# TMS320C5509A.net
KiCad netlist of a schematic drawn in Altium Designer
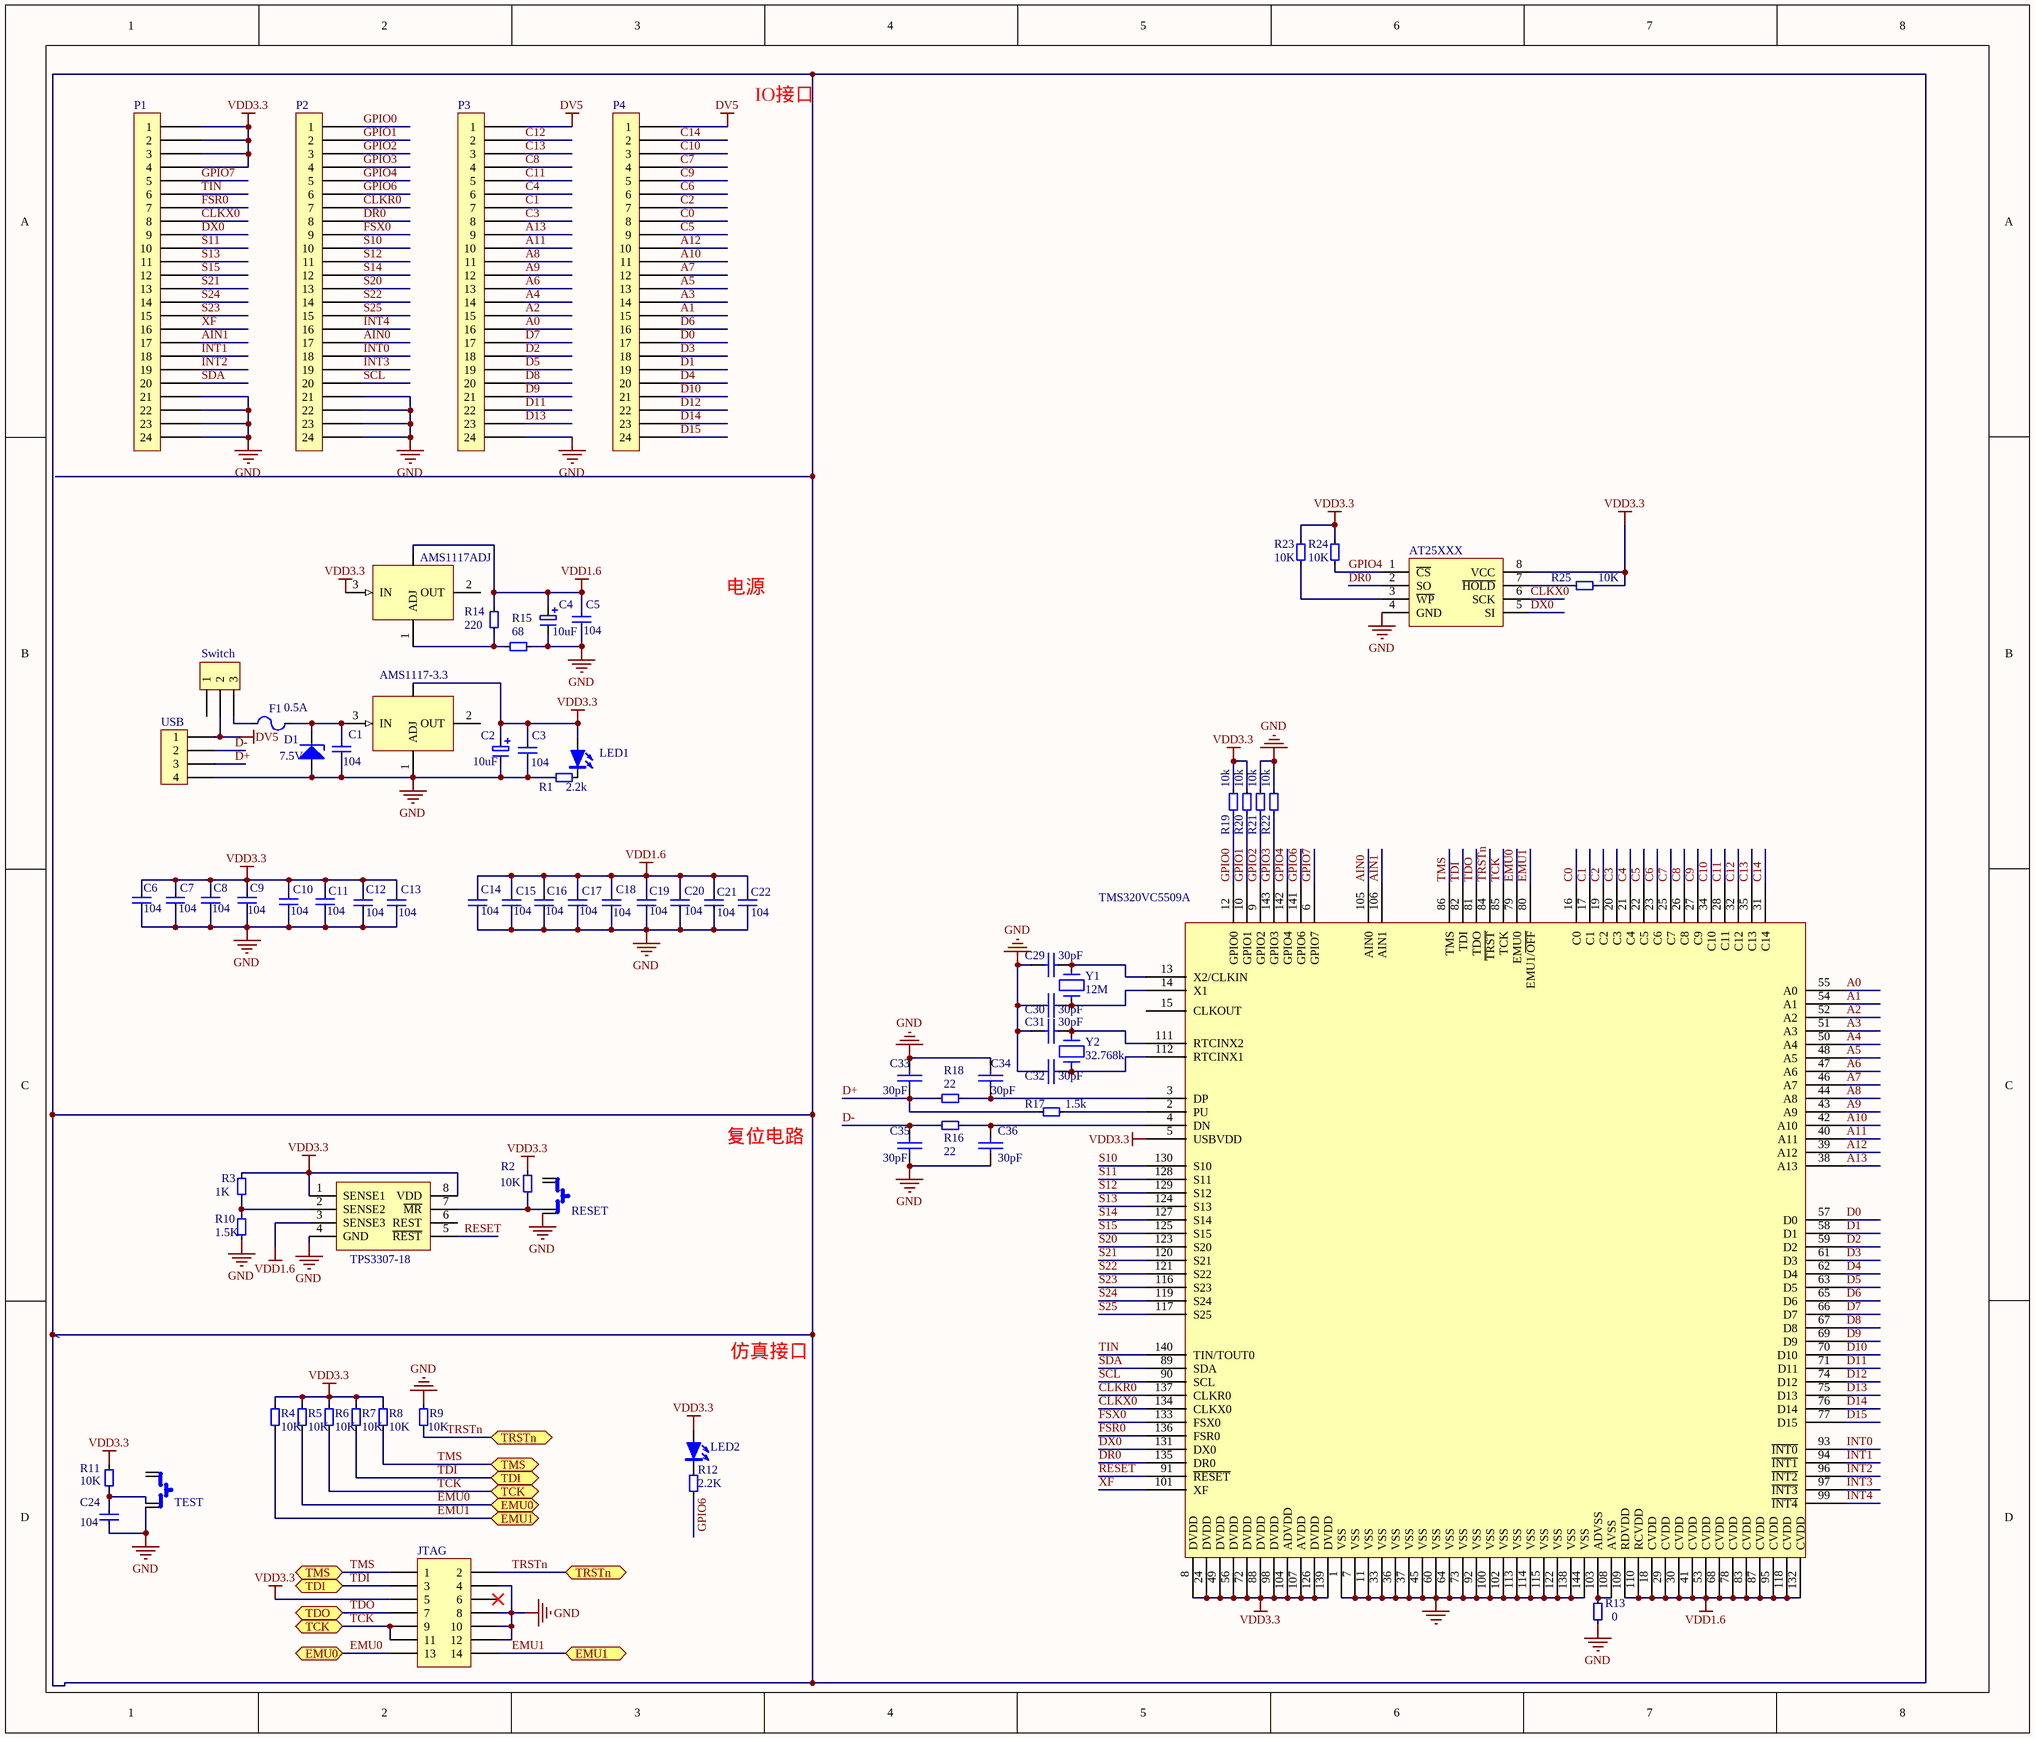
[diagram p0: TMS320C5509A.SchDoc]

(export (version "E")
  (design (tool "Eeschema 10.0.6"))
  (components
    (comp (ref "AMS1117-3.3") (value "1117") (footprint "SOT-223") (libsource (lib "电源（专用）") (part "1117")))
    (comp (ref "AMS1117ADJ") (value "1117") (footprint "SOT-223") (libsource (lib "电源（专用）") (part "1117")))
    (comp (ref "AT25XXX") (value "~") (libsource (lib "Common") (part "AT25XXX")))
    (comp (ref "C1") (value "104") (footprint "0805") (libsource (lib "电容系列") (part "C3")))
    (comp (ref "C2") (value "10uF") (footprint "CE3528") (libsource (lib "电容系列") (part "E3")))
    (comp (ref "C3") (value "104") (footprint "0805") (libsource (lib "电容系列") (part "C3")))
    (comp (ref "C4") (value "10uF") (footprint "CE3528") (libsource (lib "电容系列") (part "E3")))
    (comp (ref "C5") (value "104") (footprint "0805") (libsource (lib "电容系列") (part "C3")))
    (comp (ref "C6") (value "104") (footprint "0805") (libsource (lib "电容系列") (part "C3")))
    (comp (ref "C7") (value "104") (footprint "0805") (libsource (lib "电容系列") (part "C3")))
    (comp (ref "C8") (value "104") (footprint "0805") (libsource (lib "电容系列") (part "C3")))
    (comp (ref "C9") (value "104") (footprint "0805") (libsource (lib "电容系列") (part "C3")))
    (comp (ref "C10") (value "104") (footprint "0805") (libsource (lib "电容系列") (part "C3")))
    (comp (ref "C11") (value "104") (footprint "0805") (libsource (lib "电容系列") (part "C3")))
    (comp (ref "C12") (value "104") (footprint "0805") (libsource (lib "电容系列") (part "C3")))
    (comp (ref "C13") (value "104") (footprint "0805") (libsource (lib "电容系列") (part "C3")))
    (comp (ref "C14") (value "104") (footprint "0805") (libsource (lib "电容系列") (part "C3")))
    (comp (ref "C15") (value "104") (footprint "0805") (libsource (lib "电容系列") (part "C3")))
    (comp (ref "C16") (value "104") (footprint "0805") (libsource (lib "电容系列") (part "C3")))
    (comp (ref "C17") (value "104") (footprint "0805") (libsource (lib "电容系列") (part "C3")))
    (comp (ref "C18") (value "104") (footprint "0805") (libsource (lib "电容系列") (part "C3")))
    (comp (ref "C19") (value "104") (footprint "0805") (libsource (lib "电容系列") (part "C3")))
    (comp (ref "C20") (value "104") (footprint "0805") (libsource (lib "电容系列") (part "C3")))
    (comp (ref "C21") (value "104") (footprint "0805") (libsource (lib "电容系列") (part "C3")))
    (comp (ref "C22") (value "104") (footprint "0805") (libsource (lib "电容系列") (part "C3")))
    (comp (ref "C24") (value "104") (footprint "0805") (libsource (lib "电容系列") (part "C3")))
    (comp (ref "C29") (value "30pF") (footprint "0805") (libsource (lib "电容系列") (part "C1")))
    (comp (ref "C30") (value "30pF") (footprint "0805") (libsource (lib "电容系列") (part "C1")))
    (comp (ref "C31") (value "30pF") (footprint "0805") (libsource (lib "电容系列") (part "C1")))
    (comp (ref "C32") (value "30pF") (footprint "0805") (libsource (lib "电容系列") (part "C1")))
    (comp (ref "C33") (value "30pF") (footprint "0805") (libsource (lib "电容系列") (part "C1")))
    (comp (ref "C34") (value "30pF") (footprint "0805") (libsource (lib "电容系列") (part "C1")))
    (comp (ref "C35") (value "30pF") (footprint "0805") (libsource (lib "电容系列") (part "C1")))
    (comp (ref "C36") (value "30pF") (footprint "0805") (libsource (lib "电容系列") (part "C1")))
    (comp (ref "D1") (value "7.5V") (footprint "1206") (libsource (lib "二极管") (part "D4")))
    (comp (ref "F1") (value "0.5A") (footprint "F4532") (libsource (lib "常用库") (part "FUSE1")))
    (comp (ref "JTAG")
      (value "Header 7X2")
      (footprint "IDC14A")
      (description "Header, 7-Pin, Dual row")
      (fields (field (name "PUBLISHER") "Altium Limited"))
      (libsource (lib "myproject") (part "Header 7X2"))
    )
    (comp (ref "LED1") (value "LED2") (footprint "0805") (libsource (lib "发光管、数码管") (part "LED2")))
    (comp (ref "LED2") (value "LED2") (footprint "0805") (libsource (lib "发光管、数码管") (part "LED2")))
    (comp (ref "P1") (value "SIP24") (footprint "SIP24") (libsource (lib "SIP2.54") (part "SIP24")))
    (comp (ref "P2") (value "SIP24") (footprint "SIP24") (libsource (lib "SIP2.54") (part "SIP24")))
    (comp (ref "P3") (value "SIP24") (footprint "SIP24") (libsource (lib "SIP2.54") (part "SIP24")))
    (comp (ref "P4") (value "SIP24") (footprint "SIP24") (libsource (lib "SIP2.54") (part "SIP24")))
    (comp (ref "R1") (value "2.2k") (footprint "0805") (libsource (lib "电阻系列") (part "R3")))
    (comp (ref "R2") (value "10K") (footprint "0805") (libsource (lib "电阻系列") (part "R3")))
    (comp (ref "R3") (value "1K") (footprint "0805") (libsource (lib "电阻系列") (part "R3")))
    (comp (ref "R4") (value "10K") (footprint "0805") (libsource (lib "电阻系列") (part "R3")))
    (comp (ref "R5") (value "10K") (footprint "0805") (libsource (lib "电阻系列") (part "R3")))
    (comp (ref "R6") (value "10K") (footprint "0805") (libsource (lib "电阻系列") (part "R3")))
    (comp (ref "R7") (value "10K") (footprint "0805") (libsource (lib "电阻系列") (part "R3")))
    (comp (ref "R8") (value "10K") (footprint "0805") (libsource (lib "电阻系列") (part "R3")))
    (comp (ref "R9") (value "10K") (footprint "0805") (libsource (lib "电阻系列") (part "R3")))
    (comp (ref "R10") (value "1.5K") (footprint "0805") (libsource (lib "电阻系列") (part "R3")))
    (comp (ref "R11") (value "10K") (footprint "0805") (libsource (lib "电阻系列") (part "R3")))
    (comp (ref "R12") (value "2.2K") (footprint "0805") (libsource (lib "电阻系列") (part "R3")))
    (comp (ref "R13") (value "0") (footprint "0805") (libsource (lib "电阻系列") (part "R3")))
    (comp (ref "R14") (value "220") (footprint "0805") (libsource (lib "电阻系列") (part "R3")))
    (comp (ref "R15") (value "68") (footprint "0805") (libsource (lib "电阻系列") (part "R3")))
    (comp (ref "R16") (value "22") (footprint "0805") (libsource (lib "电阻系列") (part "R3")))
    (comp (ref "R17") (value "1.5k") (footprint "0805") (libsource (lib "电阻系列") (part "R3")))
    (comp (ref "R18") (value "22") (footprint "0805") (libsource (lib "电阻系列") (part "R3")))
    (comp (ref "R19") (value "10k") (footprint "0805") (libsource (lib "电阻系列") (part "R3")))
    (comp (ref "R20") (value "10k") (footprint "0805") (libsource (lib "电阻系列") (part "R3")))
    (comp (ref "R21") (value "10k") (footprint "0805") (libsource (lib "电阻系列") (part "R3")))
    (comp (ref "R22") (value "10k") (footprint "0805") (libsource (lib "电阻系列") (part "R3")))
    (comp (ref "R23") (value "10K") (footprint "0805") (libsource (lib "电阻系列") (part "R3")))
    (comp (ref "R24") (value "10K") (footprint "0805") (libsource (lib "电阻系列") (part "R3")))
    (comp (ref "R25") (value "10K") (footprint "0805") (libsource (lib "电阻系列") (part "R3")))
    (comp (ref "RESET") (value "KEY2") (footprint "KEY0.2'") (libsource (lib "常用库") (part "KEY2")))
    (comp (ref "Switch") (value "CON3") (footprint "船型三脚开关:5脚船型开关") (libsource (lib "常用接插件") (part "CON3")))
    (comp (ref "TEST") (value "KEY2") (footprint "KEY0.2'") (libsource (lib "常用库") (part "KEY2")))
    (comp (ref "TMS320VC5509A")
      (value "TMS320VC5509A")
      (footprint "TMS320LV5410")
      (description "TMS320VC5509")
      (libsource (lib "*") (part "TMS320VC5509A"))
    )
    (comp (ref "TPS3307-18") (value "~") (footprint "SOP8") (libsource (lib "myproject") (part "TPS3307-18")))
    (comp (ref "USB") (value "CON4") (footprint "USB2") (libsource (lib "常用接插件") (part "CON4")))
    (comp (ref "Y1") (value "12M") (footprint "CY1") (libsource (lib "常用库") (part "CY1")))
    (comp (ref "Y2") (value "32.768k") (footprint "CY1") (libsource (lib "常用库") (part "CY1")))
  )
  (nets
    (net (code "1") (name "/A0") (class "Default")
      (node (ref "P3") (pin "16") (pinfunction "16_16") (pintype "passive"))
      (node (ref "TMS320VC5509A") (pin "55") (pinfunction "A0_55") (pintype "passive"))
    )
    (net (code "2") (name "/A1") (class "Default")
      (node (ref "P4") (pin "15") (pinfunction "15_15") (pintype "passive"))
      (node (ref "TMS320VC5509A") (pin "54") (pinfunction "A1_54") (pintype "passive"))
    )
    (net (code "3") (name "/A2") (class "Default")
      (node (ref "P3") (pin "15") (pinfunction "15_15") (pintype "passive"))
      (node (ref "TMS320VC5509A") (pin "52") (pinfunction "A2_52") (pintype "passive"))
    )
    (net (code "4") (name "/A3") (class "Default")
      (node (ref "P4") (pin "14") (pinfunction "14_14") (pintype "passive"))
      (node (ref "TMS320VC5509A") (pin "51") (pinfunction "A3_51") (pintype "passive"))
    )
    (net (code "5") (name "/A4") (class "Default")
      (node (ref "P3") (pin "14") (pinfunction "14_14") (pintype "passive"))
      (node (ref "TMS320VC5509A") (pin "50") (pinfunction "A4_50") (pintype "passive"))
    )
    (net (code "6") (name "/A5") (class "Default")
      (node (ref "P4") (pin "13") (pinfunction "13_13") (pintype "passive"))
      (node (ref "TMS320VC5509A") (pin "48") (pinfunction "A5_48") (pintype "passive"))
    )
    (net (code "7") (name "/A6") (class "Default")
      (node (ref "P3") (pin "13") (pinfunction "13_13") (pintype "passive"))
      (node (ref "TMS320VC5509A") (pin "47") (pinfunction "A6_47") (pintype "passive"))
    )
    (net (code "8") (name "/A7") (class "Default")
      (node (ref "P4") (pin "12") (pinfunction "12_12") (pintype "passive"))
      (node (ref "TMS320VC5509A") (pin "46") (pinfunction "A7_46") (pintype "passive"))
    )
    (net (code "9") (name "/A8") (class "Default")
      (node (ref "P3") (pin "11") (pinfunction "11_11") (pintype "passive"))
      (node (ref "TMS320VC5509A") (pin "44") (pinfunction "A8_44") (pintype "passive"))
    )
    (net (code "10") (name "/A9") (class "Default")
      (node (ref "P3") (pin "12") (pinfunction "12_12") (pintype "passive"))
      (node (ref "TMS320VC5509A") (pin "43") (pinfunction "A9_43") (pintype "passive"))
    )
    (net (code "11") (name "/A10") (class "Default")
      (node (ref "P4") (pin "11") (pinfunction "11_11") (pintype "passive"))
      (node (ref "TMS320VC5509A") (pin "42") (pinfunction "A10_42") (pintype "passive"))
    )
    (net (code "12") (name "/A11") (class "Default")
      (node (ref "P3") (pin "10") (pinfunction "10_10") (pintype "passive"))
      (node (ref "TMS320VC5509A") (pin "40") (pinfunction "A11_40") (pintype "passive"))
    )
    (net (code "13") (name "/A12") (class "Default")
      (node (ref "P4") (pin "10") (pinfunction "10_10") (pintype "passive"))
      (node (ref "TMS320VC5509A") (pin "39") (pinfunction "A12_39") (pintype "passive"))
    )
    (net (code "14") (name "/A13") (class "Default")
      (node (ref "P3") (pin "9") (pinfunction "9_9") (pintype "passive"))
      (node (ref "TMS320VC5509A") (pin "38") (pinfunction "A13_38") (pintype "passive"))
    )
    (net (code "15") (name "/AIN0") (class "Default")
      (node (ref "P2") (pin "17") (pinfunction "17_17") (pintype "passive"))
      (node (ref "TMS320VC5509A") (pin "105") (pinfunction "AIN0_105") (pintype "passive"))
    )
    (net (code "16") (name "/AIN1") (class "Default")
      (node (ref "P1") (pin "17") (pinfunction "17_17") (pintype "passive"))
      (node (ref "TMS320VC5509A") (pin "106") (pinfunction "AIN1_106") (pintype "passive"))
    )
    (net (code "17") (name "/C0") (class "Default")
      (node (ref "P4") (pin "8") (pinfunction "8_8") (pintype "passive"))
      (node (ref "TMS320VC5509A") (pin "16") (pinfunction "C0_16") (pintype "passive"))
    )
    (net (code "18") (name "/C1") (class "Default")
      (node (ref "P3") (pin "7") (pinfunction "7_7") (pintype "passive"))
      (node (ref "TMS320VC5509A") (pin "17") (pinfunction "C1_17") (pintype "passive"))
    )
    (net (code "19") (name "/C2") (class "Default")
      (node (ref "P4") (pin "7") (pinfunction "7_7") (pintype "passive"))
      (node (ref "TMS320VC5509A") (pin "19") (pinfunction "C2_19") (pintype "passive"))
    )
    (net (code "20") (name "/C3") (class "Default")
      (node (ref "P3") (pin "8") (pinfunction "8_8") (pintype "passive"))
      (node (ref "TMS320VC5509A") (pin "20") (pinfunction "C3_20") (pintype "passive"))
    )
    (net (code "21") (name "/C4") (class "Default")
      (node (ref "P3") (pin "6") (pinfunction "6_6") (pintype "passive"))
      (node (ref "TMS320VC5509A") (pin "21") (pinfunction "C4_21") (pintype "passive"))
    )
    (net (code "22") (name "/C5") (class "Default")
      (node (ref "P4") (pin "9") (pinfunction "9_9") (pintype "passive"))
      (node (ref "TMS320VC5509A") (pin "22") (pinfunction "C5_22") (pintype "passive"))
    )
    (net (code "23") (name "/C6") (class "Default")
      (node (ref "P4") (pin "6") (pinfunction "6_6") (pintype "passive"))
      (node (ref "TMS320VC5509A") (pin "23") (pinfunction "C6_23") (pintype "passive"))
    )
    (net (code "24") (name "/C7") (class "Default")
      (node (ref "P4") (pin "4") (pinfunction "4_4") (pintype "passive"))
      (node (ref "TMS320VC5509A") (pin "25") (pinfunction "C7_25") (pintype "passive"))
    )
    (net (code "25") (name "/C8") (class "Default")
      (node (ref "P3") (pin "4") (pinfunction "4_4") (pintype "passive"))
      (node (ref "TMS320VC5509A") (pin "26") (pinfunction "C8_26") (pintype "passive"))
    )
    (net (code "26") (name "/C9") (class "Default")
      (node (ref "P4") (pin "5") (pinfunction "5_5") (pintype "passive"))
      (node (ref "TMS320VC5509A") (pin "27") (pinfunction "C9_27") (pintype "passive"))
    )
    (net (code "27") (name "/C10") (class "Default")
      (node (ref "P4") (pin "3") (pinfunction "3_3") (pintype "passive"))
      (node (ref "TMS320VC5509A") (pin "34") (pinfunction "C10_34") (pintype "passive"))
    )
    (net (code "28") (name "/C11") (class "Default")
      (node (ref "P3") (pin "5") (pinfunction "5_5") (pintype "passive"))
      (node (ref "TMS320VC5509A") (pin "28") (pinfunction "C11_28") (pintype "passive"))
    )
    (net (code "29") (name "/C12") (class "Default")
      (node (ref "P3") (pin "2") (pinfunction "2_2") (pintype "passive"))
      (node (ref "TMS320VC5509A") (pin "32") (pinfunction "C12_32") (pintype "passive"))
    )
    (net (code "30") (name "/C13") (class "Default")
      (node (ref "P3") (pin "3") (pinfunction "3_3") (pintype "passive"))
      (node (ref "TMS320VC5509A") (pin "35") (pinfunction "C13_35") (pintype "passive"))
    )
    (net (code "31") (name "/C14") (class "Default")
      (node (ref "P4") (pin "2") (pinfunction "2_2") (pintype "passive"))
      (node (ref "TMS320VC5509A") (pin "31") (pinfunction "C14_31") (pintype "passive"))
    )
    (net (code "32") (name "/CLKR0") (class "Default")
      (node (ref "P2") (pin "7") (pinfunction "7_7") (pintype "passive"))
      (node (ref "TMS320VC5509A") (pin "137") (pinfunction "CLKR0_137") (pintype "passive"))
    )
    (net (code "33") (name "/CLKX0") (class "Default")
      (node (ref "AT25XXX") (pin "6") (pinfunction "SCK_6") (pintype "passive"))
      (node (ref "P1") (pin "8") (pinfunction "8_8") (pintype "passive"))
      (node (ref "TMS320VC5509A") (pin "134") (pinfunction "CLKX0_134") (pintype "passive"))
    )
    (net (code "34") (name "/D+") (class "Default")
      (node (ref "C33") (pin "2") (pinfunction "2_2") (pintype "passive"))
      (node (ref "R17") (pin "2") (pinfunction "2_2") (pintype "passive"))
      (node (ref "R18") (pin "2") (pinfunction "2_2") (pintype "passive"))
      (node (ref "USB") (pin "3") (pinfunction "3_3") (pintype "passive"))
    )
    (net (code "35") (name "/D-") (class "Default")
      (node (ref "C35") (pin "2") (pinfunction "2_2") (pintype "passive"))
      (node (ref "R16") (pin "2") (pinfunction "2_2") (pintype "passive"))
      (node (ref "USB") (pin "2") (pinfunction "2_2") (pintype "passive"))
    )
    (net (code "36") (name "/D0") (class "Default")
      (node (ref "P4") (pin "17") (pinfunction "17_17") (pintype "passive"))
      (node (ref "TMS320VC5509A") (pin "57") (pinfunction "D0_57") (pintype "passive"))
    )
    (net (code "37") (name "/D1") (class "Default")
      (node (ref "P4") (pin "19") (pinfunction "19_19") (pintype "passive"))
      (node (ref "TMS320VC5509A") (pin "58") (pinfunction "D1_58") (pintype "passive"))
    )
    (net (code "38") (name "/D2") (class "Default")
      (node (ref "P3") (pin "18") (pinfunction "18_18") (pintype "passive"))
      (node (ref "TMS320VC5509A") (pin "59") (pinfunction "D2_59") (pintype "passive"))
    )
    (net (code "39") (name "/D3") (class "Default")
      (node (ref "P4") (pin "18") (pinfunction "18_18") (pintype "passive"))
      (node (ref "TMS320VC5509A") (pin "61") (pinfunction "D3_61") (pintype "passive"))
    )
    (net (code "40") (name "/D4") (class "Default")
      (node (ref "P4") (pin "20") (pinfunction "20_20") (pintype "passive"))
      (node (ref "TMS320VC5509A") (pin "62") (pinfunction "D4_62") (pintype "passive"))
    )
    (net (code "41") (name "/D5") (class "Default")
      (node (ref "P3") (pin "19") (pinfunction "19_19") (pintype "passive"))
      (node (ref "TMS320VC5509A") (pin "63") (pinfunction "D5_63") (pintype "passive"))
    )
    (net (code "42") (name "/D6") (class "Default")
      (node (ref "P4") (pin "16") (pinfunction "16_16") (pintype "passive"))
      (node (ref "TMS320VC5509A") (pin "65") (pinfunction "D6_65") (pintype "passive"))
    )
    (net (code "43") (name "/D7") (class "Default")
      (node (ref "P3") (pin "17") (pinfunction "17_17") (pintype "passive"))
      (node (ref "TMS320VC5509A") (pin "66") (pinfunction "D7_66") (pintype "passive"))
    )
    (net (code "44") (name "/D8") (class "Default")
      (node (ref "P3") (pin "20") (pinfunction "20_20") (pintype "passive"))
      (node (ref "TMS320VC5509A") (pin "67") (pinfunction "D8_67") (pintype "passive"))
    )
    (net (code "45") (name "/D9") (class "Default")
      (node (ref "P3") (pin "21") (pinfunction "21_21") (pintype "passive"))
      (node (ref "TMS320VC5509A") (pin "69") (pinfunction "D9_69") (pintype "passive"))
    )
    (net (code "46") (name "/D10") (class "Default")
      (node (ref "P4") (pin "21") (pinfunction "21_21") (pintype "passive"))
      (node (ref "TMS320VC5509A") (pin "70") (pinfunction "D10_70") (pintype "passive"))
    )
    (net (code "47") (name "/D11") (class "Default")
      (node (ref "P3") (pin "22") (pinfunction "22_22") (pintype "passive"))
      (node (ref "TMS320VC5509A") (pin "71") (pinfunction "D11_71") (pintype "passive"))
    )
    (net (code "48") (name "/D12") (class "Default")
      (node (ref "P4") (pin "22") (pinfunction "22_22") (pintype "passive"))
      (node (ref "TMS320VC5509A") (pin "74") (pinfunction "D12_74") (pintype "passive"))
    )
    (net (code "49") (name "/D13") (class "Default")
      (node (ref "P3") (pin "23") (pinfunction "23_23") (pintype "passive"))
      (node (ref "TMS320VC5509A") (pin "75") (pinfunction "D13_75") (pintype "passive"))
    )
    (net (code "50") (name "/D14") (class "Default")
      (node (ref "P4") (pin "23") (pinfunction "23_23") (pintype "passive"))
      (node (ref "TMS320VC5509A") (pin "76") (pinfunction "D14_76") (pintype "passive"))
    )
    (net (code "51") (name "/D15") (class "Default")
      (node (ref "P4") (pin "24") (pinfunction "24_24") (pintype "passive"))
      (node (ref "TMS320VC5509A") (pin "77") (pinfunction "D15_77") (pintype "passive"))
    )
    (net (code "52") (name "/DR0") (class "Default")
      (node (ref "AT25XXX") (pin "2") (pinfunction "SO_2") (pintype "passive"))
      (node (ref "P2") (pin "8") (pinfunction "8_8") (pintype "passive"))
      (node (ref "TMS320VC5509A") (pin "135") (pinfunction "DR0_135") (pintype "passive"))
    )
    (net (code "53") (name "/DX0") (class "Default")
      (node (ref "AT25XXX") (pin "5") (pinfunction "SI_5") (pintype "passive"))
      (node (ref "P1") (pin "9") (pinfunction "9_9") (pintype "passive"))
      (node (ref "TMS320VC5509A") (pin "131") (pinfunction "DX0_131") (pintype "passive"))
    )
    (net (code "54") (name "/EMU0") (class "Default")
      (node (ref "JTAG") (pin "13") (pinfunction "13_13") (pintype "passive"))
      (node (ref "R5") (pin "1") (pinfunction "1_1") (pintype "passive"))
      (node (ref "TMS320VC5509A") (pin "79") (pinfunction "EMU0_79") (pintype "passive"))
    )
    (net (code "55") (name "/EMU1") (class "Default")
      (node (ref "JTAG") (pin "14") (pinfunction "14_14") (pintype "passive"))
      (node (ref "R4") (pin "1") (pinfunction "1_1") (pintype "passive"))
      (node (ref "TMS320VC5509A") (pin "80") (pinfunction "EMU1/~{OFF}_80") (pintype "passive"))
    )
    (net (code "56") (name "/FSR0") (class "Default")
      (node (ref "P1") (pin "7") (pinfunction "7_7") (pintype "passive"))
      (node (ref "TMS320VC5509A") (pin "136") (pinfunction "FSR0_136") (pintype "passive"))
    )
    (net (code "57") (name "/FSX0") (class "Default")
      (node (ref "P2") (pin "9") (pinfunction "9_9") (pintype "passive"))
      (node (ref "TMS320VC5509A") (pin "133") (pinfunction "FSX0_133") (pintype "passive"))
    )
    (net (code "58") (name "/GPIO0") (class "Default")
      (node (ref "P2") (pin "1") (pinfunction "1_1") (pintype "passive"))
      (node (ref "R19") (pin "2") (pinfunction "2_2") (pintype "passive"))
      (node (ref "TMS320VC5509A") (pin "12") (pinfunction "GPIO0_12") (pintype "passive"))
    )
    (net (code "59") (name "/GPIO1") (class "Default")
      (node (ref "P2") (pin "2") (pinfunction "2_2") (pintype "passive"))
      (node (ref "R20") (pin "2") (pinfunction "2_2") (pintype "passive"))
      (node (ref "TMS320VC5509A") (pin "10") (pinfunction "GPIO1_10") (pintype "passive"))
    )
    (net (code "60") (name "/GPIO2") (class "Default")
      (node (ref "P2") (pin "3") (pinfunction "3_3") (pintype "passive"))
      (node (ref "R21") (pin "2") (pinfunction "2_2") (pintype "passive"))
      (node (ref "TMS320VC5509A") (pin "9") (pinfunction "GPIO2_9") (pintype "passive"))
    )
    (net (code "61") (name "/GPIO3") (class "Default")
      (node (ref "P2") (pin "4") (pinfunction "4_4") (pintype "passive"))
      (node (ref "R22") (pin "2") (pinfunction "2_2") (pintype "passive"))
      (node (ref "TMS320VC5509A") (pin "143") (pinfunction "GPIO3_143") (pintype "passive"))
    )
    (net (code "62") (name "/GPIO4") (class "Default")
      (node (ref "AT25XXX") (pin "1") (pinfunction "~{CS}_1") (pintype "passive"))
      (node (ref "P2") (pin "5") (pinfunction "5_5") (pintype "passive"))
      (node (ref "R24") (pin "1") (pinfunction "1_1") (pintype "passive"))
      (node (ref "TMS320VC5509A") (pin "142") (pinfunction "GPIO4_142") (pintype "passive"))
    )
    (net (code "63") (name "/GPIO6") (class "Default")
      (node (ref "P2") (pin "6") (pinfunction "6_6") (pintype "passive"))
      (node (ref "R12") (pin "2") (pinfunction "2_2") (pintype "passive"))
      (node (ref "TMS320VC5509A") (pin "141") (pinfunction "GPIO6_141") (pintype "passive"))
    )
    (net (code "64") (name "/GPIO7") (class "Default")
      (node (ref "P1") (pin "5") (pinfunction "5_5") (pintype "passive"))
      (node (ref "TMS320VC5509A") (pin "6") (pinfunction "GPIO7_6") (pintype "passive"))
    )
    (net (code "65") (name "/INT0") (class "Default")
      (node (ref "P2") (pin "18") (pinfunction "18_18") (pintype "passive"))
      (node (ref "TMS320VC5509A") (pin "93") (pinfunction "~{INT0}_93") (pintype "passive"))
    )
    (net (code "66") (name "/INT1") (class "Default")
      (node (ref "P1") (pin "18") (pinfunction "18_18") (pintype "passive"))
      (node (ref "TMS320VC5509A") (pin "94") (pinfunction "~{INT1}_94") (pintype "passive"))
    )
    (net (code "67") (name "/INT2") (class "Default")
      (node (ref "P1") (pin "19") (pinfunction "19_19") (pintype "passive"))
      (node (ref "TMS320VC5509A") (pin "96") (pinfunction "~{INT2}_96") (pintype "passive"))
    )
    (net (code "68") (name "/INT3") (class "Default")
      (node (ref "P2") (pin "19") (pinfunction "19_19") (pintype "passive"))
      (node (ref "TMS320VC5509A") (pin "97") (pinfunction "~{INT3}_97") (pintype "passive"))
    )
    (net (code "69") (name "/INT4") (class "Default")
      (node (ref "P2") (pin "16") (pinfunction "16_16") (pintype "passive"))
      (node (ref "TMS320VC5509A") (pin "99") (pinfunction "~{INT4}_99") (pintype "passive"))
    )
    (net (code "70") (name "/RESET") (class "Default")
      (node (ref "TMS320VC5509A") (pin "91") (pinfunction "~{RESET}_91") (pintype "passive"))
      (node (ref "TPS3307-18") (pin "5") (pinfunction "~{REST}_5") (pintype "passive"))
    )
    (net (code "71") (name "/S10") (class "Default")
      (node (ref "P2") (pin "10") (pinfunction "10_10") (pintype "passive"))
      (node (ref "TMS320VC5509A") (pin "130") (pinfunction "S10_130") (pintype "passive"))
    )
    (net (code "72") (name "/S11") (class "Default")
      (node (ref "P1") (pin "10") (pinfunction "10_10") (pintype "passive"))
      (node (ref "TMS320VC5509A") (pin "128") (pinfunction "S11_128") (pintype "passive"))
    )
    (net (code "73") (name "/S12") (class "Default")
      (node (ref "P2") (pin "11") (pinfunction "11_11") (pintype "passive"))
      (node (ref "TMS320VC5509A") (pin "129") (pinfunction "S12_129") (pintype "passive"))
    )
    (net (code "74") (name "/S13") (class "Default")
      (node (ref "P1") (pin "11") (pinfunction "11_11") (pintype "passive"))
      (node (ref "TMS320VC5509A") (pin "124") (pinfunction "S13_124") (pintype "passive"))
    )
    (net (code "75") (name "/S14") (class "Default")
      (node (ref "P2") (pin "12") (pinfunction "12_12") (pintype "passive"))
      (node (ref "TMS320VC5509A") (pin "127") (pinfunction "S14_127") (pintype "passive"))
    )
    (net (code "76") (name "/S15") (class "Default")
      (node (ref "P1") (pin "12") (pinfunction "12_12") (pintype "passive"))
      (node (ref "TMS320VC5509A") (pin "125") (pinfunction "S15_125") (pintype "passive"))
    )
    (net (code "77") (name "/S20") (class "Default")
      (node (ref "P2") (pin "13") (pinfunction "13_13") (pintype "passive"))
      (node (ref "TMS320VC5509A") (pin "123") (pinfunction "S20_123") (pintype "passive"))
    )
    (net (code "78") (name "/S21") (class "Default")
      (node (ref "P1") (pin "13") (pinfunction "13_13") (pintype "passive"))
      (node (ref "TMS320VC5509A") (pin "120") (pinfunction "S21_120") (pintype "passive"))
    )
    (net (code "79") (name "/S22") (class "Default")
      (node (ref "P2") (pin "14") (pinfunction "14_14") (pintype "passive"))
      (node (ref "TMS320VC5509A") (pin "121") (pinfunction "S22_121") (pintype "passive"))
    )
    (net (code "80") (name "/S23") (class "Default")
      (node (ref "P1") (pin "15") (pinfunction "15_15") (pintype "passive"))
      (node (ref "TMS320VC5509A") (pin "116") (pinfunction "S23_116") (pintype "passive"))
    )
    (net (code "81") (name "/S24") (class "Default")
      (node (ref "P1") (pin "14") (pinfunction "14_14") (pintype "passive"))
      (node (ref "TMS320VC5509A") (pin "119") (pinfunction "S24_119") (pintype "passive"))
    )
    (net (code "82") (name "/S25") (class "Default")
      (node (ref "P2") (pin "15") (pinfunction "15_15") (pintype "passive"))
      (node (ref "TMS320VC5509A") (pin "117") (pinfunction "S25_117") (pintype "passive"))
    )
    (net (code "83") (name "/SCL") (class "Default")
      (node (ref "P2") (pin "20") (pinfunction "20_20") (pintype "passive"))
      (node (ref "TMS320VC5509A") (pin "90") (pinfunction "SCL_90") (pintype "passive"))
    )
    (net (code "84") (name "/SDA") (class "Default")
      (node (ref "P1") (pin "20") (pinfunction "20_20") (pintype "passive"))
      (node (ref "TMS320VC5509A") (pin "89") (pinfunction "SDA_89") (pintype "passive"))
    )
    (net (code "85") (name "/TCK") (class "Default")
      (node (ref "JTAG") (pin "11") (pinfunction "11_11") (pintype "passive"))
      (node (ref "JTAG") (pin "9") (pinfunction "9_9") (pintype "passive"))
      (node (ref "R6") (pin "1") (pinfunction "1_1") (pintype "passive"))
      (node (ref "TMS320VC5509A") (pin "85") (pinfunction "TCK_85") (pintype "passive"))
    )
    (net (code "86") (name "/TDI") (class "Default")
      (node (ref "JTAG") (pin "3") (pinfunction "3_3") (pintype "passive"))
      (node (ref "R7") (pin "1") (pinfunction "1_1") (pintype "passive"))
      (node (ref "TMS320VC5509A") (pin "82") (pinfunction "TDI_82") (pintype "passive"))
    )
    (net (code "87") (name "/TDO") (class "Default")
      (node (ref "JTAG") (pin "7") (pinfunction "7_7") (pintype "passive"))
      (node (ref "TMS320VC5509A") (pin "81") (pinfunction "TDO_81") (pintype "passive"))
    )
    (net (code "88") (name "/TIN") (class "Default")
      (node (ref "P1") (pin "6") (pinfunction "6_6") (pintype "passive"))
      (node (ref "TMS320VC5509A") (pin "140") (pinfunction "TIN/TOUT0_140") (pintype "passive"))
    )
    (net (code "89") (name "/TMS") (class "Default")
      (node (ref "JTAG") (pin "1") (pinfunction "1_1") (pintype "passive"))
      (node (ref "R8") (pin "1") (pinfunction "1_1") (pintype "passive"))
      (node (ref "TMS320VC5509A") (pin "86") (pinfunction "TMS_86") (pintype "passive"))
    )
    (net (code "90") (name "/TRSTn") (class "Default")
      (node (ref "JTAG") (pin "2") (pinfunction "2_2") (pintype "passive"))
      (node (ref "R9") (pin "1") (pinfunction "1_1") (pintype "passive"))
      (node (ref "TMS320VC5509A") (pin "84") (pinfunction "~{TRST}_84") (pintype "passive"))
    )
    (net (code "91") (name "/XF") (class "Default")
      (node (ref "P1") (pin "16") (pinfunction "16_16") (pintype "passive"))
      (node (ref "TMS320VC5509A") (pin "101") (pinfunction "XF_101") (pintype "passive"))
    )
    (net (code "92") (name "DV5") (class "Default")
      (node (ref "P3") (pin "1") (pinfunction "1_1") (pintype "passive"))
      (node (ref "P4") (pin "1") (pinfunction "1_1") (pintype "passive"))
      (node (ref "Switch") (pin "2") (pinfunction "2_2") (pintype "passive"))
      (node (ref "USB") (pin "1") (pinfunction "1_1") (pintype "passive"))
    )
    (net (code "93") (name "GND") (class "Default")
      (node (ref "AMS1117-3.3") (pin "1") (pinfunction "ADJ_1") (pintype "power_in"))
      (node (ref "AT25XXX") (pin "4") (pinfunction "GND_4") (pintype "passive"))
      (node (ref "C1") (pin "2") (pinfunction "2_2") (pintype "passive"))
      (node (ref "C10") (pin "2") (pinfunction "2_2") (pintype "passive"))
      (node (ref "C11") (pin "2") (pinfunction "2_2") (pintype "passive"))
      (node (ref "C12") (pin "2") (pinfunction "2_2") (pintype "passive"))
      (node (ref "C13") (pin "2") (pinfunction "2_2") (pintype "passive"))
      (node (ref "C14") (pin "2") (pinfunction "2_2") (pintype "passive"))
      (node (ref "C15") (pin "2") (pinfunction "2_2") (pintype "passive"))
      (node (ref "C16") (pin "2") (pinfunction "2_2") (pintype "passive"))
      (node (ref "C17") (pin "2") (pinfunction "2_2") (pintype "passive"))
      (node (ref "C18") (pin "2") (pinfunction "2_2") (pintype "passive"))
      (node (ref "C19") (pin "2") (pinfunction "2_2") (pintype "passive"))
      (node (ref "C2") (pin "2") (pinfunction "2_2") (pintype "passive"))
      (node (ref "C20") (pin "2") (pinfunction "2_2") (pintype "passive"))
      (node (ref "C21") (pin "1") (pinfunction "1_1") (pintype "passive"))
      (node (ref "C22") (pin "1") (pinfunction "1_1") (pintype "passive"))
      (node (ref "C24") (pin "1") (pinfunction "1_1") (pintype "passive"))
      (node (ref "C29") (pin "1") (pinfunction "1_1") (pintype "passive"))
      (node (ref "C3") (pin "2") (pinfunction "2_2") (pintype "passive"))
      (node (ref "C30") (pin "1") (pinfunction "1_1") (pintype "passive"))
      (node (ref "C31") (pin "1") (pinfunction "1_1") (pintype "passive"))
      (node (ref "C32") (pin "1") (pinfunction "1_1") (pintype "passive"))
      (node (ref "C33") (pin "1") (pinfunction "1_1") (pintype "passive"))
      (node (ref "C34") (pin "2") (pinfunction "2_2") (pintype "passive"))
      (node (ref "C35") (pin "1") (pinfunction "1_1") (pintype "passive"))
      (node (ref "C36") (pin "2") (pinfunction "2_2") (pintype "passive"))
      (node (ref "C4") (pin "2") (pinfunction "2_2") (pintype "passive"))
      (node (ref "C5") (pin "2") (pinfunction "2_2") (pintype "passive"))
      (node (ref "C6") (pin "2") (pinfunction "2_2") (pintype "passive"))
      (node (ref "C7") (pin "2") (pinfunction "2_2") (pintype "passive"))
      (node (ref "C8") (pin "2") (pinfunction "2_2") (pintype "passive"))
      (node (ref "C9") (pin "2") (pinfunction "2_2") (pintype "passive"))
      (node (ref "D1") (pin "1") (pinfunction "1_1") (pintype "passive"))
      (node (ref "JTAG") (pin "10") (pinfunction "10_10") (pintype "passive"))
      (node (ref "JTAG") (pin "12") (pinfunction "12_12") (pintype "passive"))
      (node (ref "JTAG") (pin "4") (pinfunction "4_4") (pintype "passive"))
      (node (ref "JTAG") (pin "8") (pinfunction "8_8") (pintype "passive"))
      (node (ref "P1") (pin "21") (pinfunction "21_21") (pintype "passive"))
      (node (ref "P1") (pin "22") (pinfunction "22_22") (pintype "passive"))
      (node (ref "P1") (pin "23") (pinfunction "23_23") (pintype "passive"))
      (node (ref "P1") (pin "24") (pinfunction "24_24") (pintype "passive"))
      (node (ref "P2") (pin "21") (pinfunction "21_21") (pintype "passive"))
      (node (ref "P2") (pin "22") (pinfunction "22_22") (pintype "passive"))
      (node (ref "P2") (pin "23") (pinfunction "23_23") (pintype "passive"))
      (node (ref "P2") (pin "24") (pinfunction "24_24") (pintype "passive"))
      (node (ref "P3") (pin "24") (pinfunction "24_24") (pintype "passive"))
      (node (ref "R1") (pin "2") (pinfunction "2_2") (pintype "passive"))
      (node (ref "R10") (pin "2") (pinfunction "2_2") (pintype "passive"))
      (node (ref "R13") (pin "1") (pinfunction "1_1") (pintype "passive"))
      (node (ref "R15") (pin "2") (pinfunction "2_2") (pintype "passive"))
      (node (ref "R21") (pin "1") (pinfunction "1_1") (pintype "passive"))
      (node (ref "R22") (pin "1") (pinfunction "1_1") (pintype "passive"))
      (node (ref "R9") (pin "2") (pinfunction "2_2") (pintype "passive"))
      (node (ref "RESET") (pin "3") (pintype "passive"))
      (node (ref "TEST") (pin "3") (pintype "passive"))
      (node (ref "TMS320VC5509A") (pin "1") (pinfunction "VSS_1") (pintype "passive"))
      (node (ref "TMS320VC5509A") (pin "100") (pinfunction "VSS_100") (pintype "passive"))
      (node (ref "TMS320VC5509A") (pin "102") (pinfunction "VSS_102") (pintype "passive"))
      (node (ref "TMS320VC5509A") (pin "11") (pinfunction "VSS_11") (pintype "passive"))
      (node (ref "TMS320VC5509A") (pin "113") (pinfunction "VSS_113") (pintype "passive"))
      (node (ref "TMS320VC5509A") (pin "114") (pinfunction "VSS_114") (pintype "passive"))
      (node (ref "TMS320VC5509A") (pin "115") (pinfunction "VSS_115") (pintype "passive"))
      (node (ref "TMS320VC5509A") (pin "122") (pinfunction "VSS_122") (pintype "passive"))
      (node (ref "TMS320VC5509A") (pin "138") (pinfunction "VSS_138") (pintype "passive"))
      (node (ref "TMS320VC5509A") (pin "144") (pinfunction "VSS_144") (pintype "passive"))
      (node (ref "TMS320VC5509A") (pin "33") (pinfunction "VSS_33") (pintype "passive"))
      (node (ref "TMS320VC5509A") (pin "36") (pinfunction "VSS_36") (pintype "passive"))
      (node (ref "TMS320VC5509A") (pin "37") (pinfunction "VSS_37") (pintype "passive"))
      (node (ref "TMS320VC5509A") (pin "45") (pinfunction "VSS_45") (pintype "passive"))
      (node (ref "TMS320VC5509A") (pin "60") (pinfunction "VSS_60") (pintype "passive"))
      (node (ref "TMS320VC5509A") (pin "64") (pinfunction "VSS_64") (pintype "passive"))
      (node (ref "TMS320VC5509A") (pin "7") (pinfunction "VSS_7") (pintype "passive"))
      (node (ref "TMS320VC5509A") (pin "73") (pinfunction "VSS_73") (pintype "passive"))
      (node (ref "TMS320VC5509A") (pin "92") (pinfunction "VSS_92") (pintype "passive"))
      (node (ref "TPS3307-18") (pin "4") (pinfunction "GND_4") (pintype "passive"))
      (node (ref "USB") (pin "4") (pinfunction "4_4") (pintype "passive"))
    )
    (net (code "94") (name "Net-(AMS1117-3.3-IN)") (class "Default")
      (node (ref "AMS1117-3.3") (pin "3") (pinfunction "IN_3") (pintype "input"))
      (node (ref "C1") (pin "1") (pinfunction "1_1") (pintype "passive"))
      (node (ref "D1") (pin "2") (pinfunction "2_2") (pintype "passive"))
      (node (ref "F1") (pin "2") (pintype "input"))
    )
    (net (code "95") (name "Net-(AMS1117ADJ-ADJ)") (class "Default")
      (node (ref "AMS1117ADJ") (pin "1") (pinfunction "ADJ_1") (pintype "power_in"))
      (node (ref "R14") (pin "2") (pinfunction "2_2") (pintype "passive"))
      (node (ref "R15") (pin "1") (pinfunction "1_1") (pintype "passive"))
    )
    (net (code "96") (name "Net-(AT25XXX-~{HOLD})") (class "Default")
      (node (ref "AT25XXX") (pin "7") (pinfunction "~{HOLD}_7") (pintype "passive"))
      (node (ref "R25") (pin "2") (pinfunction "2_2") (pintype "passive"))
    )
    (net (code "97") (name "Net-(AT25XXX-~{WP})") (class "Default")
      (node (ref "AT25XXX") (pin "3") (pinfunction "~{WP}_3") (pintype "passive"))
      (node (ref "R23") (pin "2") (pinfunction "2_2") (pintype "passive"))
    )
    (net (code "98") (name "Net-(C24-Pad2)") (class "Default")
      (node (ref "C24") (pin "2") (pinfunction "2_2") (pintype "passive"))
      (node (ref "R11") (pin "2") (pinfunction "2_2") (pintype "passive"))
      (node (ref "TEST") (pin "4") (pintype "passive"))
    )
    (net (code "99") (name "Net-(F1-Pad1)") (class "Default")
      (node (ref "F1") (pin "1") (pintype "input"))
      (node (ref "Switch") (pin "3") (pinfunction "3_3") (pintype "passive"))
    )
    (net (code "100") (name "Net-(LED1-Pad2)") (class "Default")
      (node (ref "LED1") (pin "2") (pinfunction "2_2") (pintype "passive"))
      (node (ref "R1") (pin "1") (pinfunction "1_1") (pintype "passive"))
    )
    (net (code "101") (name "Net-(LED2-Pad2)") (class "Default")
      (node (ref "LED2") (pin "2") (pinfunction "2_2") (pintype "passive"))
      (node (ref "R12") (pin "1") (pinfunction "1_1") (pintype "passive"))
    )
    (net (code "102") (name "Net-(TMS320VC5509A-ADVSS)") (class "Default")
      (node (ref "R13") (pin "2") (pinfunction "2_2") (pintype "passive"))
      (node (ref "TMS320VC5509A") (pin "103") (pinfunction "ADVSS_103") (pintype "passive"))
      (node (ref "TMS320VC5509A") (pin "108") (pinfunction "AVSS_108") (pintype "passive"))
    )
    (net (code "103") (name "Net-(TMS320VC5509A-DN)") (class "Default")
      (node (ref "C36") (pin "1") (pinfunction "1_1") (pintype "passive"))
      (node (ref "R16") (pin "1") (pinfunction "1_1") (pintype "passive"))
      (node (ref "TMS320VC5509A") (pin "4") (pinfunction "DN_4") (pintype "passive"))
    )
    (net (code "104") (name "Net-(TMS320VC5509A-DP)") (class "Default")
      (node (ref "C34") (pin "1") (pinfunction "1_1") (pintype "passive"))
      (node (ref "R18") (pin "1") (pinfunction "1_1") (pintype "passive"))
      (node (ref "TMS320VC5509A") (pin "3") (pinfunction "DP_3") (pintype "passive"))
    )
    (net (code "105") (name "Net-(TMS320VC5509A-PU)") (class "Default")
      (node (ref "R17") (pin "1") (pinfunction "1_1") (pintype "passive"))
      (node (ref "TMS320VC5509A") (pin "2") (pinfunction "PU_2") (pintype "passive"))
    )
    (net (code "106") (name "Net-(TMS320VC5509A-RTCINX1)") (class "Default")
      (node (ref "C32") (pin "2") (pinfunction "2_2") (pintype "passive"))
      (node (ref "TMS320VC5509A") (pin "112") (pinfunction "RTCINX1_112") (pintype "passive"))
      (node (ref "Y2") (pin "2") (pinfunction "2_2") (pintype "passive"))
    )
    (net (code "107") (name "Net-(TMS320VC5509A-RTCINX2)") (class "Default")
      (node (ref "C31") (pin "2") (pinfunction "2_2") (pintype "passive"))
      (node (ref "TMS320VC5509A") (pin "111") (pinfunction "RTCINX2_111") (pintype "passive"))
      (node (ref "Y2") (pin "1") (pinfunction "1_1") (pintype "passive"))
    )
    (net (code "108") (name "Net-(TMS320VC5509A-X1)") (class "Default")
      (node (ref "C30") (pin "2") (pinfunction "2_2") (pintype "passive"))
      (node (ref "TMS320VC5509A") (pin "14") (pinfunction "X1_14") (pintype "passive"))
      (node (ref "Y1") (pin "1") (pinfunction "1_1") (pintype "passive"))
    )
    (net (code "109") (name "Net-(TMS320VC5509A-X2{slash}CLKIN)") (class "Default")
      (node (ref "C29") (pin "2") (pinfunction "2_2") (pintype "passive"))
      (node (ref "TMS320VC5509A") (pin "13") (pinfunction "X2/CLKIN_13") (pintype "passive"))
      (node (ref "Y1") (pin "2") (pinfunction "2_2") (pintype "passive"))
    )
    (net (code "110") (name "Net-(TPS3307-18-SENSE2)") (class "Default")
      (node (ref "R10") (pin "1") (pinfunction "1_1") (pintype "passive"))
      (node (ref "R3") (pin "1") (pinfunction "1_1") (pintype "passive"))
      (node (ref "TPS3307-18") (pin "2") (pinfunction "SENSE2_2") (pintype "passive"))
    )
    (net (code "111") (name "Net-(TPS3307-18-~{MR})") (class "Default")
      (node (ref "R2") (pin "2") (pinfunction "2_2") (pintype "passive"))
      (node (ref "RESET") (pin "4") (pintype "passive"))
      (node (ref "TPS3307-18") (pin "7") (pinfunction "~{MR}_7") (pintype "passive"))
    )
    (net (code "112") (name "VDD1.6") (class "Default")
      (node (ref "AMS1117ADJ") (pin "4") (pintype "passive"))
      (node (ref "C14") (pin "1") (pinfunction "1_1") (pintype "passive"))
      (node (ref "C15") (pin "1") (pinfunction "1_1") (pintype "passive"))
      (node (ref "C16") (pin "1") (pinfunction "1_1") (pintype "passive"))
      (node (ref "C17") (pin "1") (pinfunction "1_1") (pintype "passive"))
      (node (ref "C18") (pin "1") (pinfunction "1_1") (pintype "passive"))
      (node (ref "C19") (pin "1") (pinfunction "1_1") (pintype "passive"))
      (node (ref "C20") (pin "1") (pinfunction "1_1") (pintype "passive"))
      (node (ref "C21") (pin "2") (pinfunction "2_2") (pintype "passive"))
      (node (ref "C22") (pin "2") (pinfunction "2_2") (pintype "passive"))
      (node (ref "C4") (pin "1") (pinfunction "1_1") (pintype "passive"))
      (node (ref "C5") (pin "1") (pinfunction "1_1") (pintype "passive"))
      (node (ref "R14") (pin "1") (pinfunction "1_1") (pintype "passive"))
      (node (ref "TMS320VC5509A") (pin "109") (pinfunction "RDVDD_109") (pintype "passive"))
      (node (ref "TMS320VC5509A") (pin "110") (pinfunction "RCVDD_110") (pintype "passive"))
      (node (ref "TMS320VC5509A") (pin "118") (pinfunction "CVDD_118") (pintype "power_in"))
      (node (ref "TMS320VC5509A") (pin "132") (pinfunction "CVDD_132") (pintype "power_in"))
      (node (ref "TMS320VC5509A") (pin "18") (pinfunction "CVDD_18") (pintype "power_in"))
      (node (ref "TMS320VC5509A") (pin "29") (pinfunction "CVDD_29") (pintype "power_in"))
      (node (ref "TMS320VC5509A") (pin "30") (pinfunction "CVDD_30") (pintype "power_in"))
      (node (ref "TMS320VC5509A") (pin "41") (pinfunction "CVDD_41") (pintype "power_in"))
      (node (ref "TMS320VC5509A") (pin "53") (pinfunction "CVDD_53") (pintype "power_in"))
      (node (ref "TMS320VC5509A") (pin "68") (pinfunction "CVDD_68") (pintype "power_in"))
      (node (ref "TMS320VC5509A") (pin "78") (pinfunction "CVDD_78") (pintype "power_in"))
      (node (ref "TMS320VC5509A") (pin "83") (pinfunction "CVDD_83") (pintype "power_in"))
      (node (ref "TMS320VC5509A") (pin "87") (pinfunction "CVDD_87") (pintype "power_in"))
      (node (ref "TMS320VC5509A") (pin "95") (pinfunction "CVDD_95") (pintype "passive"))
      (node (ref "TPS3307-18") (pin "3") (pinfunction "SENSE3_3") (pintype "passive"))
    )
    (net (code "113") (name "VDD3.3") (class "Default")
      (node (ref "AMS1117-3.3") (pin "4") (pintype "passive"))
      (node (ref "AMS1117ADJ") (pin "3") (pinfunction "IN_3") (pintype "input"))
      (node (ref "AT25XXX") (pin "8") (pinfunction "VCC_8") (pintype "passive"))
      (node (ref "C10") (pin "1") (pinfunction "1_1") (pintype "passive"))
      (node (ref "C11") (pin "1") (pinfunction "1_1") (pintype "passive"))
      (node (ref "C12") (pin "1") (pinfunction "1_1") (pintype "passive"))
      (node (ref "C13") (pin "1") (pinfunction "1_1") (pintype "passive"))
      (node (ref "C2") (pin "1") (pinfunction "1_1") (pintype "passive"))
      (node (ref "C3") (pin "1") (pinfunction "1_1") (pintype "passive"))
      (node (ref "C6") (pin "1") (pinfunction "1_1") (pintype "passive"))
      (node (ref "C7") (pin "1") (pinfunction "1_1") (pintype "passive"))
      (node (ref "C8") (pin "1") (pinfunction "1_1") (pintype "passive"))
      (node (ref "C9") (pin "1") (pinfunction "1_1") (pintype "passive"))
      (node (ref "JTAG") (pin "5") (pinfunction "5_5") (pintype "passive"))
      (node (ref "LED1") (pin "1") (pinfunction "1_1") (pintype "passive"))
      (node (ref "LED2") (pin "1") (pinfunction "1_1") (pintype "passive"))
      (node (ref "P1") (pin "1") (pinfunction "1_1") (pintype "passive"))
      (node (ref "P1") (pin "2") (pinfunction "2_2") (pintype "passive"))
      (node (ref "P1") (pin "3") (pinfunction "3_3") (pintype "passive"))
      (node (ref "P1") (pin "4") (pinfunction "4_4") (pintype "passive"))
      (node (ref "R11") (pin "1") (pinfunction "1_1") (pintype "passive"))
      (node (ref "R19") (pin "1") (pinfunction "1_1") (pintype "passive"))
      (node (ref "R2") (pin "1") (pinfunction "1_1") (pintype "passive"))
      (node (ref "R20") (pin "1") (pinfunction "1_1") (pintype "passive"))
      (node (ref "R23") (pin "1") (pinfunction "1_1") (pintype "passive"))
      (node (ref "R24") (pin "2") (pinfunction "2_2") (pintype "passive"))
      (node (ref "R25") (pin "1") (pinfunction "1_1") (pintype "passive"))
      (node (ref "R3") (pin "2") (pinfunction "2_2") (pintype "passive"))
      (node (ref "R4") (pin "2") (pinfunction "2_2") (pintype "passive"))
      (node (ref "R5") (pin "2") (pinfunction "2_2") (pintype "passive"))
      (node (ref "R6") (pin "2") (pinfunction "2_2") (pintype "passive"))
      (node (ref "R7") (pin "2") (pinfunction "2_2") (pintype "passive"))
      (node (ref "R8") (pin "2") (pinfunction "2_2") (pintype "passive"))
      (node (ref "TMS320VC5509A") (pin "104") (pinfunction "ADVDD_104") (pintype "power_in"))
      (node (ref "TMS320VC5509A") (pin "107") (pinfunction "AVDD_107") (pintype "power_in"))
      (node (ref "TMS320VC5509A") (pin "126") (pinfunction "DVDD_126") (pintype "power_in"))
      (node (ref "TMS320VC5509A") (pin "139") (pinfunction "DVDD_139") (pintype "power_in"))
      (node (ref "TMS320VC5509A") (pin "24") (pinfunction "DVDD_24") (pintype "power_in"))
      (node (ref "TMS320VC5509A") (pin "49") (pinfunction "DVDD_49") (pintype "power_in"))
      (node (ref "TMS320VC5509A") (pin "5") (pinfunction "USBVDD_5") (pintype "passive"))
      (node (ref "TMS320VC5509A") (pin "56") (pinfunction "DVDD_56") (pintype "power_in"))
      (node (ref "TMS320VC5509A") (pin "72") (pinfunction "DVDD_72") (pintype "power_in"))
      (node (ref "TMS320VC5509A") (pin "8") (pinfunction "DVDD_8") (pintype "power_in"))
      (node (ref "TMS320VC5509A") (pin "88") (pinfunction "DVDD_88") (pintype "power_in"))
      (node (ref "TMS320VC5509A") (pin "98") (pinfunction "DVDD_98") (pintype "power_in"))
      (node (ref "TPS3307-18") (pin "1") (pinfunction "SENSE1_1") (pintype "passive"))
      (node (ref "TPS3307-18") (pin "8") (pinfunction "VDD_8") (pintype "passive"))
    )
    (net (code "114") (name "unconnected-(AMS1117-3.3-OUT-Pad2)") (class "Default")
      (node (ref "AMS1117-3.3") (pin "2") (pinfunction "OUT_2") (pintype "power_in"))
    )
    (net (code "115") (name "unconnected-(AMS1117ADJ-OUT-Pad2)") (class "Default")
      (node (ref "AMS1117ADJ") (pin "2") (pinfunction "OUT_2") (pintype "power_in"))
    )
    (net (code "116") (name "unconnected-(JTAG-Pad6)") (class "Default")
      (node (ref "JTAG") (pin "6") (pinfunction "6_6") (pintype "passive+no_connect"))
    )
    (net (code "117") (name "unconnected-(RESET-Pad1)") (class "Default")
      (node (ref "RESET") (pin "1") (pintype "passive"))
    )
    (net (code "118") (name "unconnected-(RESET-Pad2)") (class "Default")
      (node (ref "RESET") (pin "2") (pintype "passive"))
    )
    (net (code "119") (name "unconnected-(Switch-Pad1)") (class "Default")
      (node (ref "Switch") (pin "1") (pinfunction "1_1") (pintype "passive"))
    )
    (net (code "120") (name "unconnected-(TEST-Pad1)") (class "Default")
      (node (ref "TEST") (pin "1") (pintype "passive"))
    )
    (net (code "121") (name "unconnected-(TEST-Pad2)") (class "Default")
      (node (ref "TEST") (pin "2") (pintype "passive"))
    )
    (net (code "122") (name "unconnected-(TMS320VC5509A-CLKOUT-Pad15)") (class "Default")
      (node (ref "TMS320VC5509A") (pin "15") (pinfunction "CLKOUT_15") (pintype "passive"))
    )
    (net (code "123") (name "unconnected-(TPS3307-18-REST-Pad6)") (class "Default")
      (node (ref "TPS3307-18") (pin "6") (pinfunction "REST_6") (pintype "passive"))
    )
  )
)
